# CM3_CON.net
KiCad netlist of a schematic drawn in Altium Designer
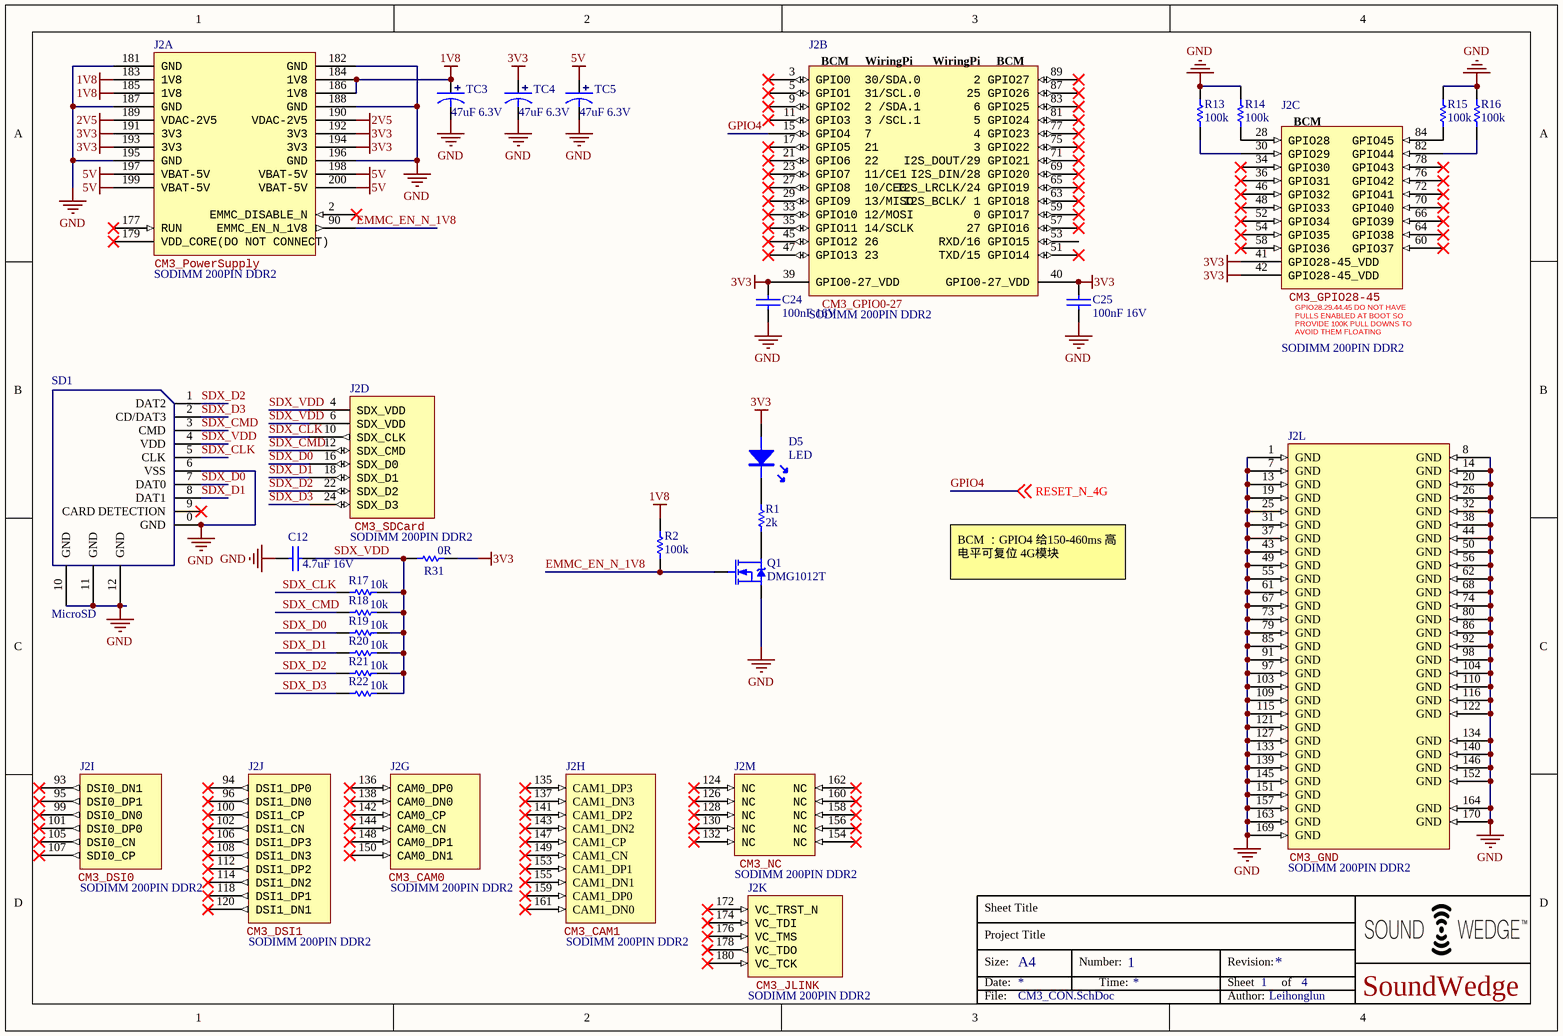
[diagram p0: CM3_CON.SchDoc]

(export (version "E")
  (design (tool "Eeschema 10.0.6"))
  (components
    (comp (ref "C12")
      (value "4.7uF 16V")
      (footprint "PCB_VPlayer:0402C")
      (libsource (lib "电容") (part "CAP-NP"))
    )
    (comp (ref "C24")
      (value "100nF 16V")
      (footprint "PCB_VPlayer:0402C")
      (libsource (lib "电容") (part "CAP-NP"))
    )
    (comp (ref "C25")
      (value "100nF 16V")
      (footprint "PCB_VPlayer:0402C")
      (libsource (lib "电容") (part "CAP-NP"))
    )
    (comp (ref "D5")
      (value "LED")
      (footprint "LED-0603G")
      (description "绿色")
      (libsource (lib "LED") (part "LED"))
    )
    (comp (ref "J2")
      (value "SODIMM 200PIN DDR2")
      (footprint "树莓派模块:SODIMM 200PIN - 5.2H")
      (libsource (lib "树莓派模块") (part "RPi-CM3"))
    )
    (comp (ref "Q1")
      (value "DMG1012T")
      (footprint "SOT523")
      (description "N沟道场效应管")
      (libsource (lib "MOS管") (part "N-MOS"))
    )
    (comp (ref "R1") (value "2k") (footprint "PCB_VPlayer:0402R") (libsource (lib "电阻") (part "RES")))
    (comp (ref "R2") (value "100k") (footprint "PCB_VPlayer:0402R") (libsource (lib "电阻") (part "RES")))
    (comp (ref "R13") (value "100k") (footprint "PCB_VPlayer:0402R") (libsource (lib "电阻") (part "RES")))
    (comp (ref "R14") (value "100k") (footprint "PCB_VPlayer:0402R") (libsource (lib "电阻") (part "RES")))
    (comp (ref "R15") (value "100k") (footprint "PCB_VPlayer:0402R") (libsource (lib "电阻") (part "RES")))
    (comp (ref "R16") (value "100k") (footprint "PCB_VPlayer:0402R") (libsource (lib "电阻") (part "RES")))
    (comp (ref "R17") (value "10k") (footprint "PCB_VPlayer:0402R") (libsource (lib "电阻") (part "RES")))
    (comp (ref "R18") (value "10k") (footprint "PCB_VPlayer:0402R") (libsource (lib "电阻") (part "RES")))
    (comp (ref "R19") (value "10k") (footprint "PCB_VPlayer:0402R") (libsource (lib "电阻") (part "RES")))
    (comp (ref "R20") (value "10k") (footprint "PCB_VPlayer:0402R") (libsource (lib "电阻") (part "RES")))
    (comp (ref "R21") (value "10k") (footprint "PCB_VPlayer:0402R") (libsource (lib "电阻") (part "RES")))
    (comp (ref "R22") (value "10k") (footprint "PCB_VPlayer:0402R") (libsource (lib "电阻") (part "RES")))
    (comp (ref "R31") (value "0R") (footprint "PCB_VPlayer:0402R") (libsource (lib "电阻") (part "RES")))
    (comp (ref "SD1")
      (value "MicroSD")
      (footprint "Micro SD")
      (description "佐田¦(自弹)TF卡座 micro sd卡座")
      (libsource (lib "SD Card") (part "MicroSD"))
    )
    (comp (ref "TC3") (value "47uF 6.3V") (footprint "TAJ-A/3216") (libsource (lib "电容") (part "TCAP")))
    (comp (ref "TC4") (value "47uF 6.3V") (footprint "TAJ-A/3216") (libsource (lib "电容") (part "TCAP")))
    (comp (ref "TC5") (value "47uF 6.3V") (footprint "TAJ-A/3216") (libsource (lib "电容") (part "TCAP")))
  )
  (nets
    (net (code "1") (name "/EMMC_EN_N_1V8") (class "Default")
      (node (ref "J2") (pin "90") (pinfunction "EMMC_EN_N_1V8_90") (pintype "output"))
      (node (ref "Q1") (pin "G") (pinfunction "G_G") (pintype "passive"))
      (node (ref "R2") (pin "1") (pinfunction "1_1") (pintype "passive"))
    )
    (net (code "2") (name "/SDX_CLK") (class "Default")
      (node (ref "J2") (pin "10") (pinfunction "SDX_CLK_10") (pintype "output"))
      (node (ref "R17") (pin "1") (pinfunction "1_1") (pintype "passive"))
      (node (ref "SD1") (pin "5") (pinfunction "CLK_5") (pintype "passive"))
    )
    (net (code "3") (name "/SDX_CMD") (class "Default")
      (node (ref "J2") (pin "12") (pinfunction "SDX_CMD_12") (pintype "bidirectional"))
      (node (ref "R18") (pin "1") (pinfunction "1_1") (pintype "passive"))
      (node (ref "SD1") (pin "3") (pinfunction "CMD_3") (pintype "passive"))
    )
    (net (code "4") (name "/SDX_D0") (class "Default")
      (node (ref "J2") (pin "16") (pinfunction "SDX_D0_16") (pintype "bidirectional"))
      (node (ref "R19") (pin "1") (pinfunction "1_1") (pintype "passive"))
      (node (ref "SD1") (pin "7") (pinfunction "DAT0_7") (pintype "passive"))
    )
    (net (code "5") (name "/SDX_D1") (class "Default")
      (node (ref "J2") (pin "18") (pinfunction "SDX_D1_18") (pintype "bidirectional"))
      (node (ref "R20") (pin "1") (pinfunction "1_1") (pintype "passive"))
      (node (ref "SD1") (pin "8") (pinfunction "DAT1_8") (pintype "passive"))
    )
    (net (code "6") (name "/SDX_D2") (class "Default")
      (node (ref "J2") (pin "22") (pinfunction "SDX_D2_22") (pintype "bidirectional"))
      (node (ref "R21") (pin "1") (pinfunction "1_1") (pintype "passive"))
      (node (ref "SD1") (pin "1") (pinfunction "DAT2_1") (pintype "passive"))
    )
    (net (code "7") (name "/SDX_D3") (class "Default")
      (node (ref "J2") (pin "24") (pinfunction "SDX_D3_24") (pintype "bidirectional"))
      (node (ref "R22") (pin "1") (pinfunction "1_1") (pintype "passive"))
      (node (ref "SD1") (pin "2") (pinfunction "CD/DAT3_2") (pintype "passive"))
    )
    (net (code "8") (name "/SDX_VDD") (class "Default")
      (node (ref "C12") (pin "2") (pinfunction "2_2") (pintype "passive"))
      (node (ref "J2") (pin "4") (pinfunction "SDX_VDD_4") (pintype "power_in"))
      (node (ref "J2") (pin "6") (pinfunction "SDX_VDD_6") (pintype "power_in"))
      (node (ref "R17") (pin "2") (pinfunction "2_2") (pintype "passive"))
      (node (ref "R18") (pin "2") (pinfunction "2_2") (pintype "passive"))
      (node (ref "R19") (pin "2") (pinfunction "2_2") (pintype "passive"))
      (node (ref "R20") (pin "2") (pinfunction "2_2") (pintype "passive"))
      (node (ref "R21") (pin "2") (pinfunction "2_2") (pintype "passive"))
      (node (ref "R22") (pin "2") (pinfunction "2_2") (pintype "passive"))
      (node (ref "R31") (pin "1") (pinfunction "1_1") (pintype "passive"))
      (node (ref "SD1") (pin "4") (pinfunction "VDD_4") (pintype "passive"))
    )
    (net (code "9") (name "1V8") (class "Default")
      (node (ref "J2") (pin "183") (pinfunction "1V8_183") (pintype "power_in"))
      (node (ref "J2") (pin "184") (pinfunction "1V8_184") (pintype "power_in"))
      (node (ref "J2") (pin "185") (pinfunction "1V8_185") (pintype "power_in"))
      (node (ref "J2") (pin "186") (pinfunction "1V8_186") (pintype "power_in"))
      (node (ref "R2") (pin "2") (pinfunction "2_2") (pintype "passive"))
      (node (ref "TC3") (pin "1") (pinfunction "1_1") (pintype "passive"))
    )
    (net (code "10") (name "2V5") (class "Default")
      (node (ref "J2") (pin "189") (pinfunction "VDAC-2V5_189") (pintype "power_in"))
      (node (ref "J2") (pin "190") (pinfunction "VDAC-2V5_190") (pintype "power_in"))
    )
    (net (code "11") (name "3V3") (class "Default")
      (node (ref "C24") (pin "2") (pinfunction "2_2") (pintype "passive"))
      (node (ref "C25") (pin "2") (pinfunction "2_2") (pintype "passive"))
      (node (ref "D5") (pin "A") (pinfunction "A_A") (pintype "passive"))
      (node (ref "J2") (pin "191") (pinfunction "3V3_191") (pintype "power_in"))
      (node (ref "J2") (pin "192") (pinfunction "3V3_192") (pintype "power_in"))
      (node (ref "J2") (pin "193") (pinfunction "3V3_193") (pintype "power_in"))
      (node (ref "J2") (pin "194") (pinfunction "3V3_194") (pintype "power_in"))
      (node (ref "J2") (pin "39") (pinfunction "GPIO0-27_VDD_39") (pintype "power_in"))
      (node (ref "J2") (pin "40") (pinfunction "GPIO0-27_VDD_40") (pintype "power_in"))
      (node (ref "J2") (pin "41") (pinfunction "GPIO28-45_VDD_41") (pintype "power_in"))
      (node (ref "J2") (pin "42") (pinfunction "GPIO28-45_VDD_42") (pintype "power_in"))
      (node (ref "R31") (pin "2") (pinfunction "2_2") (pintype "passive"))
      (node (ref "TC4") (pin "1") (pinfunction "1_1") (pintype "passive"))
    )
    (net (code "12") (name "5V") (class "Default")
      (node (ref "J2") (pin "197") (pinfunction "VBAT-5V_197") (pintype "power_in"))
      (node (ref "J2") (pin "198") (pinfunction "VBAT-5V_198") (pintype "power_in"))
      (node (ref "J2") (pin "199") (pinfunction "VBAT-5V_199") (pintype "power_in"))
      (node (ref "J2") (pin "200") (pinfunction "VBAT-5V_200") (pintype "power_in"))
      (node (ref "TC5") (pin "1") (pinfunction "1_1") (pintype "passive"))
    )
    (net (code "13") (name "GND") (class "Default")
      (node (ref "C12") (pin "1") (pinfunction "1_1") (pintype "passive"))
      (node (ref "C24") (pin "1") (pinfunction "1_1") (pintype "passive"))
      (node (ref "C25") (pin "1") (pinfunction "1_1") (pintype "passive"))
      (node (ref "J2") (pin "1") (pinfunction "GND_1") (pintype "input"))
      (node (ref "J2") (pin "103") (pinfunction "GND_103") (pintype "input"))
      (node (ref "J2") (pin "104") (pinfunction "GND_104") (pintype "input"))
      (node (ref "J2") (pin "109") (pinfunction "GND_109") (pintype "input"))
      (node (ref "J2") (pin "110") (pinfunction "GND_110") (pintype "input"))
      (node (ref "J2") (pin "115") (pinfunction "GND_115") (pintype "input"))
      (node (ref "J2") (pin "116") (pinfunction "GND_116") (pintype "input"))
      (node (ref "J2") (pin "121") (pinfunction "GND_121") (pintype "input"))
      (node (ref "J2") (pin "122") (pinfunction "GND_122") (pintype "input"))
      (node (ref "J2") (pin "127") (pinfunction "GND_127") (pintype "input"))
      (node (ref "J2") (pin "13") (pinfunction "GND_13") (pintype "input"))
      (node (ref "J2") (pin "133") (pinfunction "GND_133") (pintype "input"))
      (node (ref "J2") (pin "134") (pinfunction "GND_134") (pintype "input"))
      (node (ref "J2") (pin "139") (pinfunction "GND_139") (pintype "input"))
      (node (ref "J2") (pin "14") (pinfunction "GND_14") (pintype "input"))
      (node (ref "J2") (pin "140") (pinfunction "GND_140") (pintype "input"))
      (node (ref "J2") (pin "145") (pinfunction "GND_145") (pintype "input"))
      (node (ref "J2") (pin "146") (pinfunction "GND_146") (pintype "input"))
      (node (ref "J2") (pin "151") (pinfunction "GND_151") (pintype "input"))
      (node (ref "J2") (pin "152") (pinfunction "GND_152") (pintype "input"))
      (node (ref "J2") (pin "157") (pinfunction "GND_157") (pintype "input"))
      (node (ref "J2") (pin "163") (pinfunction "GND_163") (pintype "input"))
      (node (ref "J2") (pin "164") (pinfunction "GND_164") (pintype "input"))
      (node (ref "J2") (pin "169") (pinfunction "GND_169") (pintype "input"))
      (node (ref "J2") (pin "170") (pinfunction "GND_170") (pintype "input"))
      (node (ref "J2") (pin "181") (pinfunction "GND_181") (pintype "power_in"))
      (node (ref "J2") (pin "182") (pinfunction "GND_182") (pintype "power_in"))
      (node (ref "J2") (pin "187") (pinfunction "GND_187") (pintype "power_in"))
      (node (ref "J2") (pin "188") (pinfunction "GND_188") (pintype "power_in"))
      (node (ref "J2") (pin "19") (pinfunction "GND_19") (pintype "input"))
      (node (ref "J2") (pin "195") (pinfunction "GND_195") (pintype "power_in"))
      (node (ref "J2") (pin "196") (pinfunction "GND_196") (pintype "power_in"))
      (node (ref "J2") (pin "20") (pinfunction "GND_20") (pintype "input"))
      (node (ref "J2") (pin "25") (pinfunction "GND_25") (pintype "input"))
      (node (ref "J2") (pin "26") (pinfunction "GND_26") (pintype "input"))
      (node (ref "J2") (pin "31") (pinfunction "GND_31") (pintype "input"))
      (node (ref "J2") (pin "32") (pinfunction "GND_32") (pintype "input"))
      (node (ref "J2") (pin "37") (pinfunction "GND_37") (pintype "input"))
      (node (ref "J2") (pin "38") (pinfunction "GND_38") (pintype "input"))
      (node (ref "J2") (pin "43") (pinfunction "GND_43") (pintype "input"))
      (node (ref "J2") (pin "44") (pinfunction "GND_44") (pintype "input"))
      (node (ref "J2") (pin "49") (pinfunction "GND_49") (pintype "input"))
      (node (ref "J2") (pin "50") (pinfunction "GND_50") (pintype "input"))
      (node (ref "J2") (pin "55") (pinfunction "GND_55") (pintype "input"))
      (node (ref "J2") (pin "56") (pinfunction "GND_56") (pintype "input"))
      (node (ref "J2") (pin "61") (pinfunction "GND_61") (pintype "input"))
      (node (ref "J2") (pin "62") (pinfunction "GND_62") (pintype "input"))
      (node (ref "J2") (pin "67") (pinfunction "GND_67") (pintype "input"))
      (node (ref "J2") (pin "68") (pinfunction "GND_68") (pintype "input"))
      (node (ref "J2") (pin "7") (pinfunction "GND_7") (pintype "input"))
      (node (ref "J2") (pin "73") (pinfunction "GND_73") (pintype "input"))
      (node (ref "J2") (pin "74") (pinfunction "GND_74") (pintype "input"))
      (node (ref "J2") (pin "79") (pinfunction "GND_79") (pintype "input"))
      (node (ref "J2") (pin "8") (pinfunction "GND_8") (pintype "input"))
      (node (ref "J2") (pin "80") (pinfunction "GND_80") (pintype "input"))
      (node (ref "J2") (pin "85") (pinfunction "GND_85") (pintype "input"))
      (node (ref "J2") (pin "86") (pinfunction "GND_86") (pintype "input"))
      (node (ref "J2") (pin "91") (pinfunction "GND_91") (pintype "input"))
      (node (ref "J2") (pin "92") (pinfunction "GND_92") (pintype "input"))
      (node (ref "J2") (pin "97") (pinfunction "GND_97") (pintype "input"))
      (node (ref "J2") (pin "98") (pinfunction "GND_98") (pintype "input"))
      (node (ref "Q1") (pin "S") (pinfunction "S_S") (pintype "passive"))
      (node (ref "R13") (pin "2") (pinfunction "2_2") (pintype "passive"))
      (node (ref "R14") (pin "2") (pinfunction "2_2") (pintype "passive"))
      (node (ref "R15") (pin "2") (pinfunction "2_2") (pintype "passive"))
      (node (ref "R16") (pin "2") (pinfunction "2_2") (pintype "passive"))
      (node (ref "SD1") (pin "0") (pinfunction "GND_0") (pintype "passive"))
      (node (ref "SD1") (pin "10") (pinfunction "GND_10") (pintype "passive"))
      (node (ref "SD1") (pin "11") (pinfunction "GND_11") (pintype "passive"))
      (node (ref "SD1") (pin "12") (pinfunction "GND_12") (pintype "passive"))
      (node (ref "SD1") (pin "6") (pinfunction "VSS_6") (pintype "passive"))
      (node (ref "TC3") (pin "2") (pinfunction "2_2") (pintype "passive"))
      (node (ref "TC4") (pin "2") (pinfunction "2_2") (pintype "passive"))
      (node (ref "TC5") (pin "2") (pinfunction "2_2") (pintype "passive"))
    )
    (net (code "14") (name "Net-(D5-PadK)") (class "Default")
      (node (ref "D5") (pin "K") (pinfunction "K_K") (pintype "passive"))
      (node (ref "R1") (pin "1") (pinfunction "1_1") (pintype "passive"))
    )
    (net (code "15") (name "Net-(J2C-GPIO28)") (class "Default")
      (node (ref "J2") (pin "28") (pinfunction "GPIO28_28") (pintype "input"))
      (node (ref "R14") (pin "1") (pinfunction "1_1") (pintype "passive"))
    )
    (net (code "16") (name "Net-(J2C-GPIO29)") (class "Default")
      (node (ref "J2") (pin "30") (pinfunction "GPIO29_30") (pintype "input"))
      (node (ref "R13") (pin "1") (pinfunction "1_1") (pintype "passive"))
    )
    (net (code "17") (name "Net-(J2C-GPIO44)") (class "Default")
      (node (ref "J2") (pin "82") (pinfunction "GPIO44_82") (pintype "input"))
      (node (ref "R16") (pin "1") (pinfunction "1_1") (pintype "passive"))
    )
    (net (code "18") (name "Net-(J2C-GPIO45)") (class "Default")
      (node (ref "J2") (pin "84") (pinfunction "GPIO45_84") (pintype "input"))
      (node (ref "R15") (pin "1") (pinfunction "1_1") (pintype "passive"))
    )
    (net (code "19") (name "Net-(Q1-PadD)") (class "Default")
      (node (ref "Q1") (pin "D") (pinfunction "D_D") (pintype "passive"))
      (node (ref "R1") (pin "2") (pinfunction "2_2") (pintype "passive"))
    )
    (net (code "20") (name "RESET_N_4G") (class "Default")
      (node (ref "J2") (pin "15") (pinfunction "GPIO4__7_15") (pintype "bidirectional"))
    )
    (net (code "21") (name "unconnected-(J2A-EMMC_DISABLE_N-Pad2)") (class "Default")
      (node (ref "J2") (pin "2") (pinfunction "EMMC_DISABLE_N_2") (pintype "input+no_connect"))
    )
    (net (code "22") (name "unconnected-(J2A-RUN-Pad177)") (class "Default")
      (node (ref "J2") (pin "177") (pinfunction "RUN_177") (pintype "input+no_connect"))
    )
    (net (code "23") (name "unconnected-(J2A-VDD_CORE(DO_NOT_CONNECT)-Pad179)") (class "Default")
      (node (ref "J2") (pin "179") (pinfunction "VDD_CORE(DO_NOT_CONNECT)_179") (pintype "power_in+no_connect"))
    )
    (net (code "24") (name "unconnected-(J2B-0_GPIO17-Pad59)") (class "Default")
      (node (ref "J2") (pin "59") (pinfunction "0_GPIO17_59") (pintype "bidirectional+no_connect"))
    )
    (net (code "25") (name "unconnected-(J2B-2_GPIO27-Pad89)") (class "Default")
      (node (ref "J2") (pin "89") (pinfunction "2_GPIO27_89") (pintype "bidirectional+no_connect"))
    )
    (net (code "26") (name "unconnected-(J2B-3_GPIO22-Pad75)") (class "Default")
      (node (ref "J2") (pin "75") (pinfunction "3_GPIO22_75") (pintype "bidirectional+no_connect"))
    )
    (net (code "27") (name "unconnected-(J2B-4_GPIO23-Pad77)") (class "Default")
      (node (ref "J2") (pin "77") (pinfunction "4_GPIO23_77") (pintype "bidirectional+no_connect"))
    )
    (net (code "28") (name "unconnected-(J2B-5_GPIO24-Pad81)") (class "Default")
      (node (ref "J2") (pin "81") (pinfunction "5_GPIO24_81") (pintype "bidirectional+no_connect"))
    )
    (net (code "29") (name "unconnected-(J2B-6_GPIO25-Pad83)") (class "Default")
      (node (ref "J2") (pin "83") (pinfunction "6_GPIO25_83") (pintype "bidirectional+no_connect"))
    )
    (net (code "30") (name "unconnected-(J2B-25_GPIO26-Pad87)") (class "Default")
      (node (ref "J2") (pin "87") (pinfunction "25_GPIO26_87") (pintype "bidirectional+no_connect"))
    )
    (net (code "31") (name "unconnected-(J2B-27_GPIO16-Pad57)") (class "Default")
      (node (ref "J2") (pin "57") (pinfunction "27_GPIO16_57") (pintype "bidirectional+no_connect"))
    )
    (net (code "32") (name "unconnected-(J2B-GPIO0__30{slash}SDA.0-Pad3)") (class "Default")
      (node (ref "J2") (pin "3") (pinfunction "GPIO0__30/SDA.0_3") (pintype "bidirectional+no_connect"))
    )
    (net (code "33") (name "unconnected-(J2B-GPIO1__31{slash}SCL.0-Pad5)") (class "Default")
      (node (ref "J2") (pin "5") (pinfunction "GPIO1__31/SCL.0_5") (pintype "bidirectional+no_connect"))
    )
    (net (code "34") (name "unconnected-(J2B-GPIO2__2_{slash}SDA.1-Pad9)") (class "Default")
      (node (ref "J2") (pin "9") (pinfunction "GPIO2__2_/SDA.1_9") (pintype "bidirectional+no_connect"))
    )
    (net (code "35") (name "unconnected-(J2B-GPIO3__3_{slash}SCL.1-Pad11)") (class "Default")
      (node (ref "J2") (pin "11") (pinfunction "GPIO3__3_/SCL.1_11") (pintype "bidirectional+no_connect"))
    )
    (net (code "36") (name "unconnected-(J2B-GPIO5__21-Pad17)") (class "Default")
      (node (ref "J2") (pin "17") (pinfunction "GPIO5__21_17") (pintype "bidirectional+no_connect"))
    )
    (net (code "37") (name "unconnected-(J2B-GPIO6__22-Pad21)") (class "Default")
      (node (ref "J2") (pin "21") (pinfunction "GPIO6__22_21") (pintype "bidirectional+no_connect"))
    )
    (net (code "38") (name "unconnected-(J2B-GPIO7__11{slash}CE1-Pad23)") (class "Default")
      (node (ref "J2") (pin "23") (pinfunction "GPIO7__11/CE1_23") (pintype "bidirectional+no_connect"))
    )
    (net (code "39") (name "unconnected-(J2B-GPIO8__10{slash}CE0-Pad27)") (class "Default")
      (node (ref "J2") (pin "27") (pinfunction "GPIO8__10/CE0_27") (pintype "bidirectional+no_connect"))
    )
    (net (code "40") (name "unconnected-(J2B-GPIO9__13{slash}MISO-Pad29)") (class "Default")
      (node (ref "J2") (pin "29") (pinfunction "GPIO9__13/MISO_29") (pintype "bidirectional+no_connect"))
    )
    (net (code "41") (name "unconnected-(J2B-GPIO10_12{slash}MOSI-Pad33)") (class "Default")
      (node (ref "J2") (pin "33") (pinfunction "GPIO10_12/MOSI_33") (pintype "bidirectional+no_connect"))
    )
    (net (code "42") (name "unconnected-(J2B-GPIO11_14{slash}SCLK-Pad35)") (class "Default")
      (node (ref "J2") (pin "35") (pinfunction "GPIO11_14/SCLK_35") (pintype "bidirectional+no_connect"))
    )
    (net (code "43") (name "unconnected-(J2B-GPIO12_26-Pad45)") (class "Default")
      (node (ref "J2") (pin "45") (pinfunction "GPIO12_26_45") (pintype "bidirectional+no_connect"))
    )
    (net (code "44") (name "unconnected-(J2B-GPIO13_23-Pad47)") (class "Default")
      (node (ref "J2") (pin "47") (pinfunction "GPIO13_23_47") (pintype "bidirectional+no_connect"))
    )
    (net (code "45") (name "unconnected-(J2B-I2S_BCLK{slash}_1_GPIO18-Pad63)") (class "Default")
      (node (ref "J2") (pin "63") (pinfunction "I2S_BCLK/_1_GPIO18_63") (pintype "bidirectional+no_connect"))
    )
    (net (code "46") (name "unconnected-(J2B-I2S_DIN{slash}28_GPIO20-Pad69)") (class "Default")
      (node (ref "J2") (pin "69") (pinfunction "I2S_DIN/28_GPIO20_69") (pintype "bidirectional+no_connect"))
    )
    (net (code "47") (name "unconnected-(J2B-I2S_DOUT{slash}29_GPIO21-Pad71)") (class "Default")
      (node (ref "J2") (pin "71") (pinfunction "I2S_DOUT/29_GPIO21_71") (pintype "bidirectional+no_connect"))
    )
    (net (code "48") (name "unconnected-(J2B-I2S_LRCLK{slash}24_GPIO19-Pad65)") (class "Default")
      (node (ref "J2") (pin "65") (pinfunction "I2S_LRCLK/24_GPIO19_65") (pintype "bidirectional+no_connect"))
    )
    (net (code "49") (name "unconnected-(J2B-RXD{slash}16_GPIO15-Pad53)") (class "Default")
      (node (ref "J2") (pin "53") (pinfunction "RXD/16_GPIO15_53") (pintype "bidirectional"))
    )
    (net (code "50") (name "unconnected-(J2B-TXD{slash}15_GPIO14-Pad51)") (class "Default")
      (node (ref "J2") (pin "51") (pinfunction "TXD/15_GPIO14_51") (pintype "bidirectional+no_connect"))
    )
    (net (code "51") (name "unconnected-(J2C-GPIO30-Pad34)") (class "Default")
      (node (ref "J2") (pin "34") (pinfunction "GPIO30_34") (pintype "input+no_connect"))
    )
    (net (code "52") (name "unconnected-(J2C-GPIO31-Pad36)") (class "Default")
      (node (ref "J2") (pin "36") (pinfunction "GPIO31_36") (pintype "input+no_connect"))
    )
    (net (code "53") (name "unconnected-(J2C-GPIO32-Pad46)") (class "Default")
      (node (ref "J2") (pin "46") (pinfunction "GPIO32_46") (pintype "input+no_connect"))
    )
    (net (code "54") (name "unconnected-(J2C-GPIO33-Pad48)") (class "Default")
      (node (ref "J2") (pin "48") (pinfunction "GPIO33_48") (pintype "input+no_connect"))
    )
    (net (code "55") (name "unconnected-(J2C-GPIO34-Pad52)") (class "Default")
      (node (ref "J2") (pin "52") (pinfunction "GPIO34_52") (pintype "input+no_connect"))
    )
    (net (code "56") (name "unconnected-(J2C-GPIO35-Pad54)") (class "Default")
      (node (ref "J2") (pin "54") (pinfunction "GPIO35_54") (pintype "input+no_connect"))
    )
    (net (code "57") (name "unconnected-(J2C-GPIO36-Pad58)") (class "Default")
      (node (ref "J2") (pin "58") (pinfunction "GPIO36_58") (pintype "input+no_connect"))
    )
    (net (code "58") (name "unconnected-(J2C-GPIO37-Pad60)") (class "Default")
      (node (ref "J2") (pin "60") (pinfunction "GPIO37_60") (pintype "input+no_connect"))
    )
    (net (code "59") (name "unconnected-(J2C-GPIO38-Pad64)") (class "Default")
      (node (ref "J2") (pin "64") (pinfunction "GPIO38_64") (pintype "input+no_connect"))
    )
    (net (code "60") (name "unconnected-(J2C-GPIO39-Pad66)") (class "Default")
      (node (ref "J2") (pin "66") (pinfunction "GPIO39_66") (pintype "input+no_connect"))
    )
    (net (code "61") (name "unconnected-(J2C-GPIO40-Pad70)") (class "Default")
      (node (ref "J2") (pin "70") (pinfunction "GPIO40_70") (pintype "input+no_connect"))
    )
    (net (code "62") (name "unconnected-(J2C-GPIO41-Pad72)") (class "Default")
      (node (ref "J2") (pin "72") (pinfunction "GPIO41_72") (pintype "input+no_connect"))
    )
    (net (code "63") (name "unconnected-(J2C-GPIO42-Pad76)") (class "Default")
      (node (ref "J2") (pin "76") (pinfunction "GPIO42_76") (pintype "input+no_connect"))
    )
    (net (code "64") (name "unconnected-(J2C-GPIO43-Pad78)") (class "Default")
      (node (ref "J2") (pin "78") (pinfunction "GPIO43_78") (pintype "input+no_connect"))
    )
    (net (code "65") (name "unconnected-(J2G-CAM0_CN-Pad144)") (class "Default")
      (node (ref "J2") (pin "144") (pinfunction "CAM0_CN_144") (pintype "input+no_connect"))
    )
    (net (code "66") (name "unconnected-(J2G-CAM0_CP-Pad142)") (class "Default")
      (node (ref "J2") (pin "142") (pinfunction "CAM0_CP_142") (pintype "input+no_connect"))
    )
    (net (code "67") (name "unconnected-(J2G-CAM0_DN0-Pad138)") (class "Default")
      (node (ref "J2") (pin "138") (pinfunction "CAM0_DN0_138") (pintype "input+no_connect"))
    )
    (net (code "68") (name "unconnected-(J2G-CAM0_DN1-Pad150)") (class "Default")
      (node (ref "J2") (pin "150") (pinfunction "CAM0_DN1_150") (pintype "input+no_connect"))
    )
    (net (code "69") (name "unconnected-(J2G-CAM0_DP0-Pad136)") (class "Default")
      (node (ref "J2") (pin "136") (pinfunction "CAM0_DP0_136") (pintype "input+no_connect"))
    )
    (net (code "70") (name "unconnected-(J2G-CAM0_DP1-Pad148)") (class "Default")
      (node (ref "J2") (pin "148") (pinfunction "CAM0_DP1_148") (pintype "input+no_connect"))
    )
    (net (code "71") (name "unconnected-(J2H-CAM1_CN-Pad149)") (class "Default")
      (node (ref "J2") (pin "149") (pinfunction "CAM1_CN_149") (pintype "input+no_connect"))
    )
    (net (code "72") (name "unconnected-(J2H-CAM1_CP-Pad147)") (class "Default")
      (node (ref "J2") (pin "147") (pinfunction "CAM1_CP_147") (pintype "input+no_connect"))
    )
    (net (code "73") (name "unconnected-(J2H-CAM1_DN0-Pad161)") (class "Default")
      (node (ref "J2") (pin "161") (pinfunction "CAM1_DN0_161") (pintype "input+no_connect"))
    )
    (net (code "74") (name "unconnected-(J2H-CAM1_DN1-Pad155)") (class "Default")
      (node (ref "J2") (pin "155") (pinfunction "CAM1_DN1_155") (pintype "input+no_connect"))
    )
    (net (code "75") (name "unconnected-(J2H-CAM1_DN2-Pad143)") (class "Default")
      (node (ref "J2") (pin "143") (pinfunction "CAM1_DN2_143") (pintype "input+no_connect"))
    )
    (net (code "76") (name "unconnected-(J2H-CAM1_DN3-Pad137)") (class "Default")
      (node (ref "J2") (pin "137") (pinfunction "CAM1_DN3_137") (pintype "input+no_connect"))
    )
    (net (code "77") (name "unconnected-(J2H-CAM1_DP0-Pad159)") (class "Default")
      (node (ref "J2") (pin "159") (pinfunction "CAM1_DP0_159") (pintype "input+no_connect"))
    )
    (net (code "78") (name "unconnected-(J2H-CAM1_DP1-Pad153)") (class "Default")
      (node (ref "J2") (pin "153") (pinfunction "CAM1_DP1_153") (pintype "input+no_connect"))
    )
    (net (code "79") (name "unconnected-(J2H-CAM1_DP2-Pad141)") (class "Default")
      (node (ref "J2") (pin "141") (pinfunction "CAM1_DP2_141") (pintype "input+no_connect"))
    )
    (net (code "80") (name "unconnected-(J2H-CAM1_DP3-Pad135)") (class "Default")
      (node (ref "J2") (pin "135") (pinfunction "CAM1_DP3_135") (pintype "input+no_connect"))
    )
    (net (code "81") (name "unconnected-(J2I-DSI0_CN-Pad105)") (class "Default")
      (node (ref "J2") (pin "105") (pinfunction "DSI0_CN_105") (pintype "output+no_connect"))
    )
    (net (code "82") (name "unconnected-(J2I-DSI0_DN0-Pad99)") (class "Default")
      (node (ref "J2") (pin "99") (pinfunction "DSI0_DN0_99") (pintype "output+no_connect"))
    )
    (net (code "83") (name "unconnected-(J2I-DSI0_DN1-Pad93)") (class "Default")
      (node (ref "J2") (pin "93") (pinfunction "DSI0_DN1_93") (pintype "output+no_connect"))
    )
    (net (code "84") (name "unconnected-(J2I-DSI0_DP0-Pad101)") (class "Default")
      (node (ref "J2") (pin "101") (pinfunction "DSI0_DP0_101") (pintype "output+no_connect"))
    )
    (net (code "85") (name "unconnected-(J2I-DSI0_DP1-Pad95)") (class "Default")
      (node (ref "J2") (pin "95") (pinfunction "DSI0_DP1_95") (pintype "output+no_connect"))
    )
    (net (code "86") (name "unconnected-(J2I-SDI0_CP-Pad107)") (class "Default")
      (node (ref "J2") (pin "107") (pinfunction "SDI0_CP_107") (pintype "output+no_connect"))
    )
    (net (code "87") (name "unconnected-(J2J-DSI1_CN-Pad102)") (class "Default")
      (node (ref "J2") (pin "102") (pinfunction "DSI1_CN_102") (pintype "output+no_connect"))
    )
    (net (code "88") (name "unconnected-(J2J-DSI1_CP-Pad100)") (class "Default")
      (node (ref "J2") (pin "100") (pinfunction "DSI1_CP_100") (pintype "output+no_connect"))
    )
    (net (code "89") (name "unconnected-(J2J-DSI1_DN0-Pad96)") (class "Default")
      (node (ref "J2") (pin "96") (pinfunction "DSI1_DN0_96") (pintype "output+no_connect"))
    )
    (net (code "90") (name "unconnected-(J2J-DSI1_DN1-Pad120)") (class "Default")
      (node (ref "J2") (pin "120") (pinfunction "DSI1_DN1_120") (pintype "output+no_connect"))
    )
    (net (code "91") (name "unconnected-(J2J-DSI1_DN2-Pad114)") (class "Default")
      (node (ref "J2") (pin "114") (pinfunction "DSI1_DN2_114") (pintype "output+no_connect"))
    )
    (net (code "92") (name "unconnected-(J2J-DSI1_DN3-Pad108)") (class "Default")
      (node (ref "J2") (pin "108") (pinfunction "DSI1_DN3_108") (pintype "output+no_connect"))
    )
    (net (code "93") (name "unconnected-(J2J-DSI1_DP0-Pad94)") (class "Default")
      (node (ref "J2") (pin "94") (pinfunction "DSI1_DP0_94") (pintype "output+no_connect"))
    )
    (net (code "94") (name "unconnected-(J2J-DSI1_DP1-Pad118)") (class "Default")
      (node (ref "J2") (pin "118") (pinfunction "DSI1_DP1_118") (pintype "output+no_connect"))
    )
    (net (code "95") (name "unconnected-(J2J-DSI1_DP2-Pad112)") (class "Default")
      (node (ref "J2") (pin "112") (pinfunction "DSI1_DP2_112") (pintype "output+no_connect"))
    )
    (net (code "96") (name "unconnected-(J2J-DSI1_DP3-Pad106)") (class "Default")
      (node (ref "J2") (pin "106") (pinfunction "DSI1_DP3_106") (pintype "output+no_connect"))
    )
    (net (code "97") (name "unconnected-(J2K-VC_TCK-Pad180)") (class "Default")
      (node (ref "J2") (pin "180") (pinfunction "VC_TCK_180") (pintype "input+no_connect"))
    )
    (net (code "98") (name "unconnected-(J2K-VC_TDI-Pad174)") (class "Default")
      (node (ref "J2") (pin "174") (pinfunction "VC_TDI_174") (pintype "input+no_connect"))
    )
    (net (code "99") (name "unconnected-(J2K-VC_TDO-Pad178)") (class "Default")
      (node (ref "J2") (pin "178") (pinfunction "VC_TDO_178") (pintype "output+no_connect"))
    )
    (net (code "100") (name "unconnected-(J2K-VC_TMS-Pad176)") (class "Default")
      (node (ref "J2") (pin "176") (pinfunction "VC_TMS_176") (pintype "input+no_connect"))
    )
    (net (code "101") (name "unconnected-(J2K-VC_TRST_N-Pad172)") (class "Default")
      (node (ref "J2") (pin "172") (pinfunction "VC_TRST_N_172") (pintype "input+no_connect"))
    )
    (net (code "102") (name "unconnected-(J2M-NC-Pad124)") (class "Default")
      (node (ref "J2") (pin "124") (pinfunction "NC_124") (pintype "input+no_connect"))
    )
    (net (code "103") (name "unconnected-(J2M-NC-Pad126)") (class "Default")
      (node (ref "J2") (pin "126") (pinfunction "NC_126") (pintype "input+no_connect"))
    )
    (net (code "104") (name "unconnected-(J2M-NC-Pad128)") (class "Default")
      (node (ref "J2") (pin "128") (pinfunction "NC_128") (pintype "input+no_connect"))
    )
    (net (code "105") (name "unconnected-(J2M-NC-Pad130)") (class "Default")
      (node (ref "J2") (pin "130") (pinfunction "NC_130") (pintype "input+no_connect"))
    )
    (net (code "106") (name "unconnected-(J2M-NC-Pad132)") (class "Default")
      (node (ref "J2") (pin "132") (pinfunction "NC_132") (pintype "input+no_connect"))
    )
    (net (code "107") (name "unconnected-(J2M-NC-Pad154)") (class "Default")
      (node (ref "J2") (pin "154") (pinfunction "NC_154") (pintype "input+no_connect"))
    )
    (net (code "108") (name "unconnected-(J2M-NC-Pad156)") (class "Default")
      (node (ref "J2") (pin "156") (pinfunction "NC_156") (pintype "input+no_connect"))
    )
    (net (code "109") (name "unconnected-(J2M-NC-Pad158)") (class "Default")
      (node (ref "J2") (pin "158") (pinfunction "NC_158") (pintype "input+no_connect"))
    )
    (net (code "110") (name "unconnected-(J2M-NC-Pad160)") (class "Default")
      (node (ref "J2") (pin "160") (pinfunction "NC_160") (pintype "input+no_connect"))
    )
    (net (code "111") (name "unconnected-(J2M-NC-Pad162)") (class "Default")
      (node (ref "J2") (pin "162") (pinfunction "NC_162") (pintype "input+no_connect"))
    )
    (net (code "112") (name "unconnected-(SD1-CARD_DETECTION-Pad9)") (class "Default")
      (node (ref "SD1") (pin "9") (pinfunction "CARD_DETECTION_9") (pintype "passive+no_connect"))
    )
  )
)
